# 2_1.net
KiCad netlist of a schematic drawn in Altium Designer
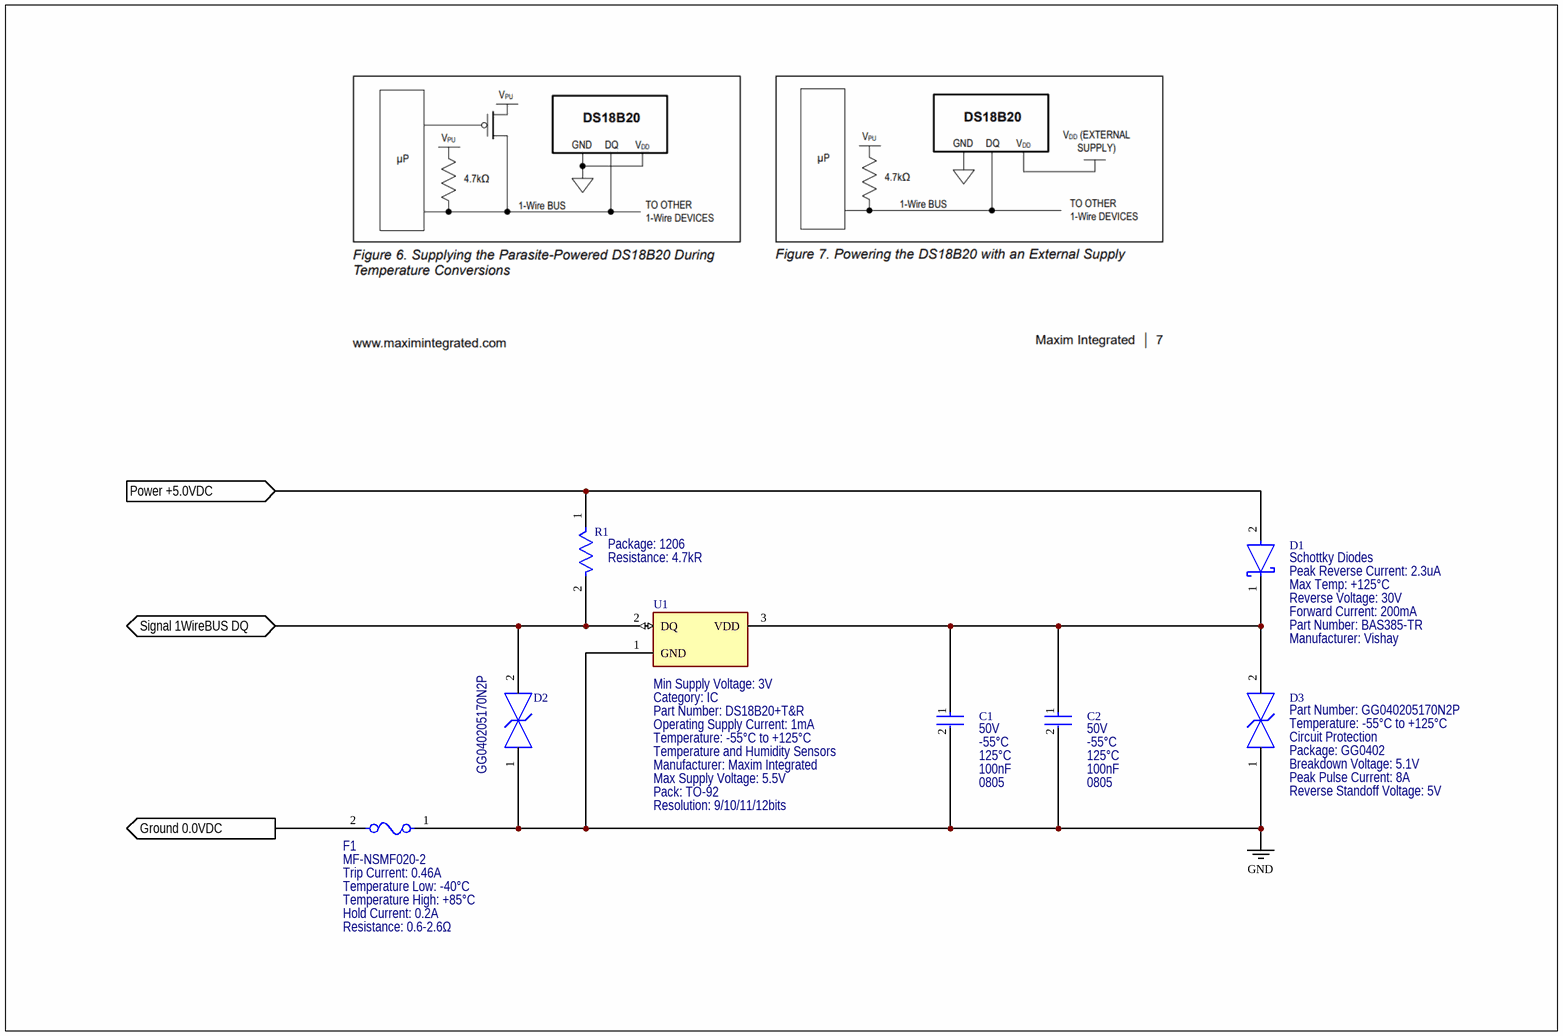
[diagram p0: 2,ФБ1,Чертеж,Схема_принципиальная.SchDoc]

(export (version "E")
  (design (tool "Eeschema 10.0.6"))
  (components
    (comp (ref "C1")
      (value "GCD21BR71H104KA01L")
      (footprint "FP-GCD21B-0_15-IPC_C")
      (description "Chip Multilayer Ceramic Capacitors for Automotive, 0805, 0.10uF, X7R, 15%, 10%, 50V, Grade 1")
      (fields
        (field (name "VOLTAGE RATING") "50V")
        (field (name "MIN OPERATING TEMPERATURE") "-55°C")
        (field (name "MAX OPERATING TEMPERATURE") "125°C")
        (field (name "CAPACITANCE") "100nF")
        (field (name "CASE CODE (IMPERIAL)") "0805")
        (field (name "TOLERANCE") "10%")
      )
      (libsource (lib "Altium Content Vault") (part "b4654b650e69147ec39a6b967a45e02"))
    )
    (comp (ref "C2")
      (value "GCD21BR71H104KA01L")
      (footprint "FP-GCD21B-0_15-IPC_C")
      (description "Chip Multilayer Ceramic Capacitors for Automotive, 0805, 0.10uF, X7R, 15%, 10%, 50V, Grade 1")
      (fields
        (field (name "VOLTAGE RATING") "50V")
        (field (name "MIN OPERATING TEMPERATURE") "-55°C")
        (field (name "MAX OPERATING TEMPERATURE") "125°C")
        (field (name "CAPACITANCE") "100nF")
        (field (name "CASE CODE (IMPERIAL)") "0805")
        (field (name "TOLERANCE") "10%")
      )
      (libsource (lib "Altium Content Vault") (part "b4654b650e69147ec39a6b967a45e02"))
    )
    (comp (ref "D1")
      (value "BAS385-TR")
      (footprint "FP-6_560-5007_01-4-MFG")
      (description "DIODE SCHOTTKY 30V 200MA MICMELF")
      (fields
        (field (name "DEVICE CLASS L3") "Schottky Diodes")
        (field (name "PEAK REVERSE CURRENT") "2.3uA")
        (field (name "MAX TEMP") "+125°C")
        (field (name "REVERSE VOLTAGE") "30V")
        (field (name "OCTOPART") "https://octopart.com/bas385-tr-vishay-55507548")
        (field (name "FORWARD CURRENT") "200mA")
        (field (name "PART NUMBER") "BAS385-TR")
        (field (name "MANUFACTURER") "Vishay")
      )
      (libsource (lib "Altium Content Vault") (part "1d6ec82d83fb6aee721767c19dac4b9"))
    )
    (comp (ref "D2")
      (value "GG040205170N2P")
      (footprint "FP-GG0402-MFG")
      (description "TVS DIODE 5V 10V 0402")
      (fields
        (field (name "PART NUMBER") "GG040205170N2P")
        (field (name "OCTOPART") "https://octopart.com/gg040205170n2p-avx-81066082")
        (field (name "MANUFACTURER") "AVX")
      )
      (libsource (lib "Altium Content Vault") (part "11bd9d59d340f0612179daf16ad9b72"))
    )
    (comp (ref "D3")
      (value "GG040205170N2P")
      (footprint "FP-GG0402-MFG")
      (description "TVS DIODE 5V 10V 0402")
      (fields
        (field (name "PART NUMBER") "GG040205170N2P")
        (field (name "TEMPERATURE") "-55°C to +125°C")
        (field (name "OCTOPART") "https://octopart.com/gg040205170n2p-avx-81066082")
        (field (name "MANUFACTURER") "AVX")
        (field (name "DEVICE CLASS L1") "Circuit Protection")
        (field (name "PACKAGE") "GG0402")
        (field (name "BREAKDOWN VOLTAGE") "5.1V")
        (field (name "PEAK PULSE CURRENT") "8A")
        (field (name "REVERSE STANDOFF VOLTAGE") "5V")
      )
      (libsource (lib "Altium Content Vault") (part "11bd9d59d340f0612179daf16ad9b72"))
    )
    (comp (ref "F1")
      (value "MF-NSMF020-2")
      (footprint "FP-MF-NSMF020-2-MFG")
      (description "PTC RESET FUSE 24V 200MA 1206")
      (fields
        (field (name "TRIP CURRENT") "0.46A")
        (field (name "TEMPERATURE LOW") "-40°C")
        (field (name "TEMPERATURE HIGH") "+85°C")
        (field (name "HOLD CURRENT") "0.2A")
        (field (name "MANUFACTURER") "Bourns")
        (field (name "OCTOPART") "https://octopart.com/mf-nsmf020-2-bourns-94649")
        (field (name "RESISTANCE") "0.6-2.6Ω")
      )
      (libsource (lib "Altium Content Vault") (part "5bcf9b9f640e542cf0359d10258e979"))
    )
    (comp (ref "R1")
      (value "RC3216F472CS")
      (footprint "FP-RC3216-IPC_A")
      (description "Res Thick Film 1206 4.7kΩ 1% 0.25W ±100ppm/°C Molded SMD T/R")
      (fields
        (field (name "PACKAGE") "1206")
        (field (name "TOLERANCE") "1%")
        (field (name "RESISTANCE") "4.7kR")
      )
      (libsource (lib "Altium Content Vault") (part "1029c3af85768c4190bb7ad29bc67b5"))
    )
    (comp (ref "U1")
      (value "DS18B20+T&R")
      (footprint "FP-Q3-4-MFG")
      (description "SENSOR DIGITAL -55C-125C TO92-3")
      (fields
        (field (name "PACK") "TO-92")
        (field (name "MIN SUPPLY VOLTAGE") "3V")
        (field (name "OCTOPART") "https://octopart.com/ds18b20%2Bt%26r-maxim+integrated-10547047")
        (field (name "CATEGORY") "IC")
        (field (name "PART NUMBER") "DS18B20+T&R")
        (field (name "OPERATING SUPPLY CURRENT") "1mA")
        (field (name "TEMPERATURE") "-55°C to +125°C")
        (field (name "DEVICE CLASS L2") "Temperature and Humidity Sensors")
        (field (name "MANUFACTURER") "Maxim Integrated")
        (field (name "MAX SUPPLY VOLTAGE") "5.5V")
        (field (name "RESOLUTION") "9/10/11/12bits")
      )
      (libsource (lib "Altium Content Vault") (part "e4eb22da2d5f2b096fc4053ffedf8c8"))
    )
  )
  (nets
    (net (code "1") (name "/Ground 0.0VDC") (class "Default")
      (node (ref "F1") (pin "2") (pinfunction "2_2") (pintype "passive"))
    )
    (net (code "2") (name "/Power +5.0VDC") (class "Default")
      (node (ref "D1") (pin "2") (pinfunction "A_2") (pintype "passive"))
      (node (ref "R1") (pin "1") (pinfunction "1_1") (pintype "passive"))
    )
    (net (code "3") (name "/Signal 1WireBUS DQ") (class "Default")
      (node (ref "D2") (pin "2") (pinfunction "2_2") (pintype "passive"))
      (node (ref "R1") (pin "2") (pinfunction "2_2") (pintype "passive"))
      (node (ref "U1") (pin "2") (pinfunction "DQ_2") (pintype "bidirectional"))
    )
    (net (code "4") (name "GND") (class "Default")
      (node (ref "C1") (pin "2") (pinfunction "2_2") (pintype "passive"))
      (node (ref "C2") (pin "2") (pinfunction "2_2") (pintype "passive"))
      (node (ref "D2") (pin "1") (pinfunction "1_1") (pintype "passive"))
      (node (ref "D3") (pin "1") (pinfunction "1_1") (pintype "passive"))
      (node (ref "F1") (pin "1") (pinfunction "1_1") (pintype "passive"))
      (node (ref "U1") (pin "1") (pinfunction "GND_1") (pintype "power_in"))
    )
    (net (code "5") (name "Net-(D1-C)") (class "Default")
      (node (ref "C1") (pin "1") (pinfunction "1_1") (pintype "passive"))
      (node (ref "C2") (pin "1") (pinfunction "1_1") (pintype "passive"))
      (node (ref "D1") (pin "1") (pinfunction "C_1") (pintype "passive"))
      (node (ref "D3") (pin "2") (pinfunction "2_2") (pintype "passive"))
      (node (ref "U1") (pin "3") (pinfunction "VDD_3") (pintype "power_in"))
    )
  )
)
